# arduino_power_supply.net
KiCad netlist of a schematic drawn in EAGLE
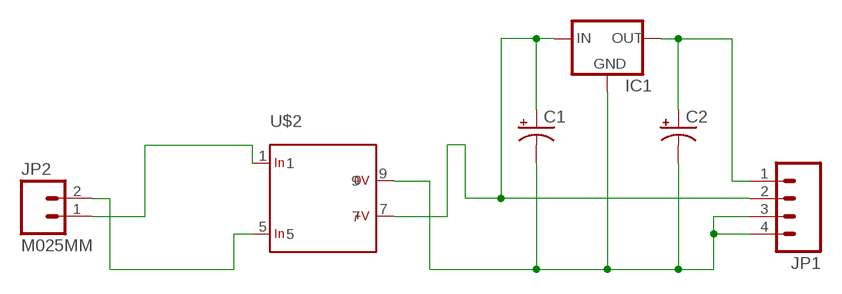
[diagram p0: schematic, sheet 1]

(export (version "E")
  (design (tool "Eeschema 10.0.6"))
  (components
    (comp (ref "C1")
      (value "CAP_POLPTH2")
      (footprint "eagle-import:CPOL-RADIAL-10UF-25V")
      (libsource (lib "eagle-import") (part "CAP_POLPTH2"))
    )
    (comp (ref "C2")
      (value "CAP_POLPTH2")
      (footprint "eagle-import:CPOL-RADIAL-10UF-25V")
      (libsource (lib "eagle-import") (part "CAP_POLPTH2"))
    )
    (comp (ref "IC1")
      (value "78XXS")
      (footprint "eagle-import:78XXS")
      (libsource (lib "eagle-import") (part "78XXS"))
    )
    (comp (ref "JP1")
      (value "M04PTH")
      (footprint "eagle-import:1X04")
      (libsource (lib "eagle-import") (part "M04PTH"))
    )
    (comp (ref "JP2")
      (value "M025MM")
      (footprint "eagle-import:SCREWTERMINAL-5MM-2")
      (libsource (lib "eagle-import") (part "M025MM"))
    )
    (comp (ref "U$2")
      (value "SINGLE")
      (footprint "eagle-import:1")
      (libsource (lib "eagle-import") (part "SINGLE"))
    )
  )
  (nets
    (net (code "1") (name "Net-(C1-+)") (class "Default")
      (node (ref "C1") (pin "1") (pinfunction "+_1") (pintype "passive"))
      (node (ref "IC1") (pin "IN") (pinfunction "IN_IN") (pintype "input"))
      (node (ref "JP1") (pin "2") (pinfunction "2_2") (pintype "passive"))
      (node (ref "U$2") (pin "7") (pinfunction "7_7") (pintype "output"))
    )
    (net (code "2") (name "Net-(C1--)") (class "Default")
      (node (ref "C1") (pin "2") (pinfunction "-_2") (pintype "passive"))
      (node (ref "C2") (pin "2") (pinfunction "-_2") (pintype "passive"))
      (node (ref "IC1") (pin "GND") (pinfunction "GND_GND") (pintype "input"))
      (node (ref "JP1") (pin "3") (pinfunction "3_3") (pintype "passive"))
      (node (ref "JP1") (pin "4") (pinfunction "4_4") (pintype "passive"))
      (node (ref "U$2") (pin "9") (pinfunction "9_9") (pintype "output"))
    )
    (net (code "3") (name "Net-(C2-+)") (class "Default")
      (node (ref "C2") (pin "1") (pinfunction "+_1") (pintype "passive"))
      (node (ref "IC1") (pin "OUT") (pinfunction "OUT_OUT") (pintype "passive"))
      (node (ref "JP1") (pin "1") (pinfunction "1_1") (pintype "passive"))
    )
    (net (code "4") (name "Net-(JP2-Pad1)") (class "Default")
      (node (ref "JP2") (pin "1") (pinfunction "1_1") (pintype "passive"))
      (node (ref "U$2") (pin "1") (pinfunction "1_1") (pintype "input"))
    )
    (net (code "5") (name "Net-(JP2-Pad2)") (class "Default")
      (node (ref "JP2") (pin "2") (pinfunction "2_2") (pintype "passive"))
      (node (ref "U$2") (pin "5") (pinfunction "5_5") (pintype "input"))
    )
  )
)
